# reTerm-HW-M-IOLINK-SUPPLY.net
KiCad netlist of a schematic drawn in Altium Designer
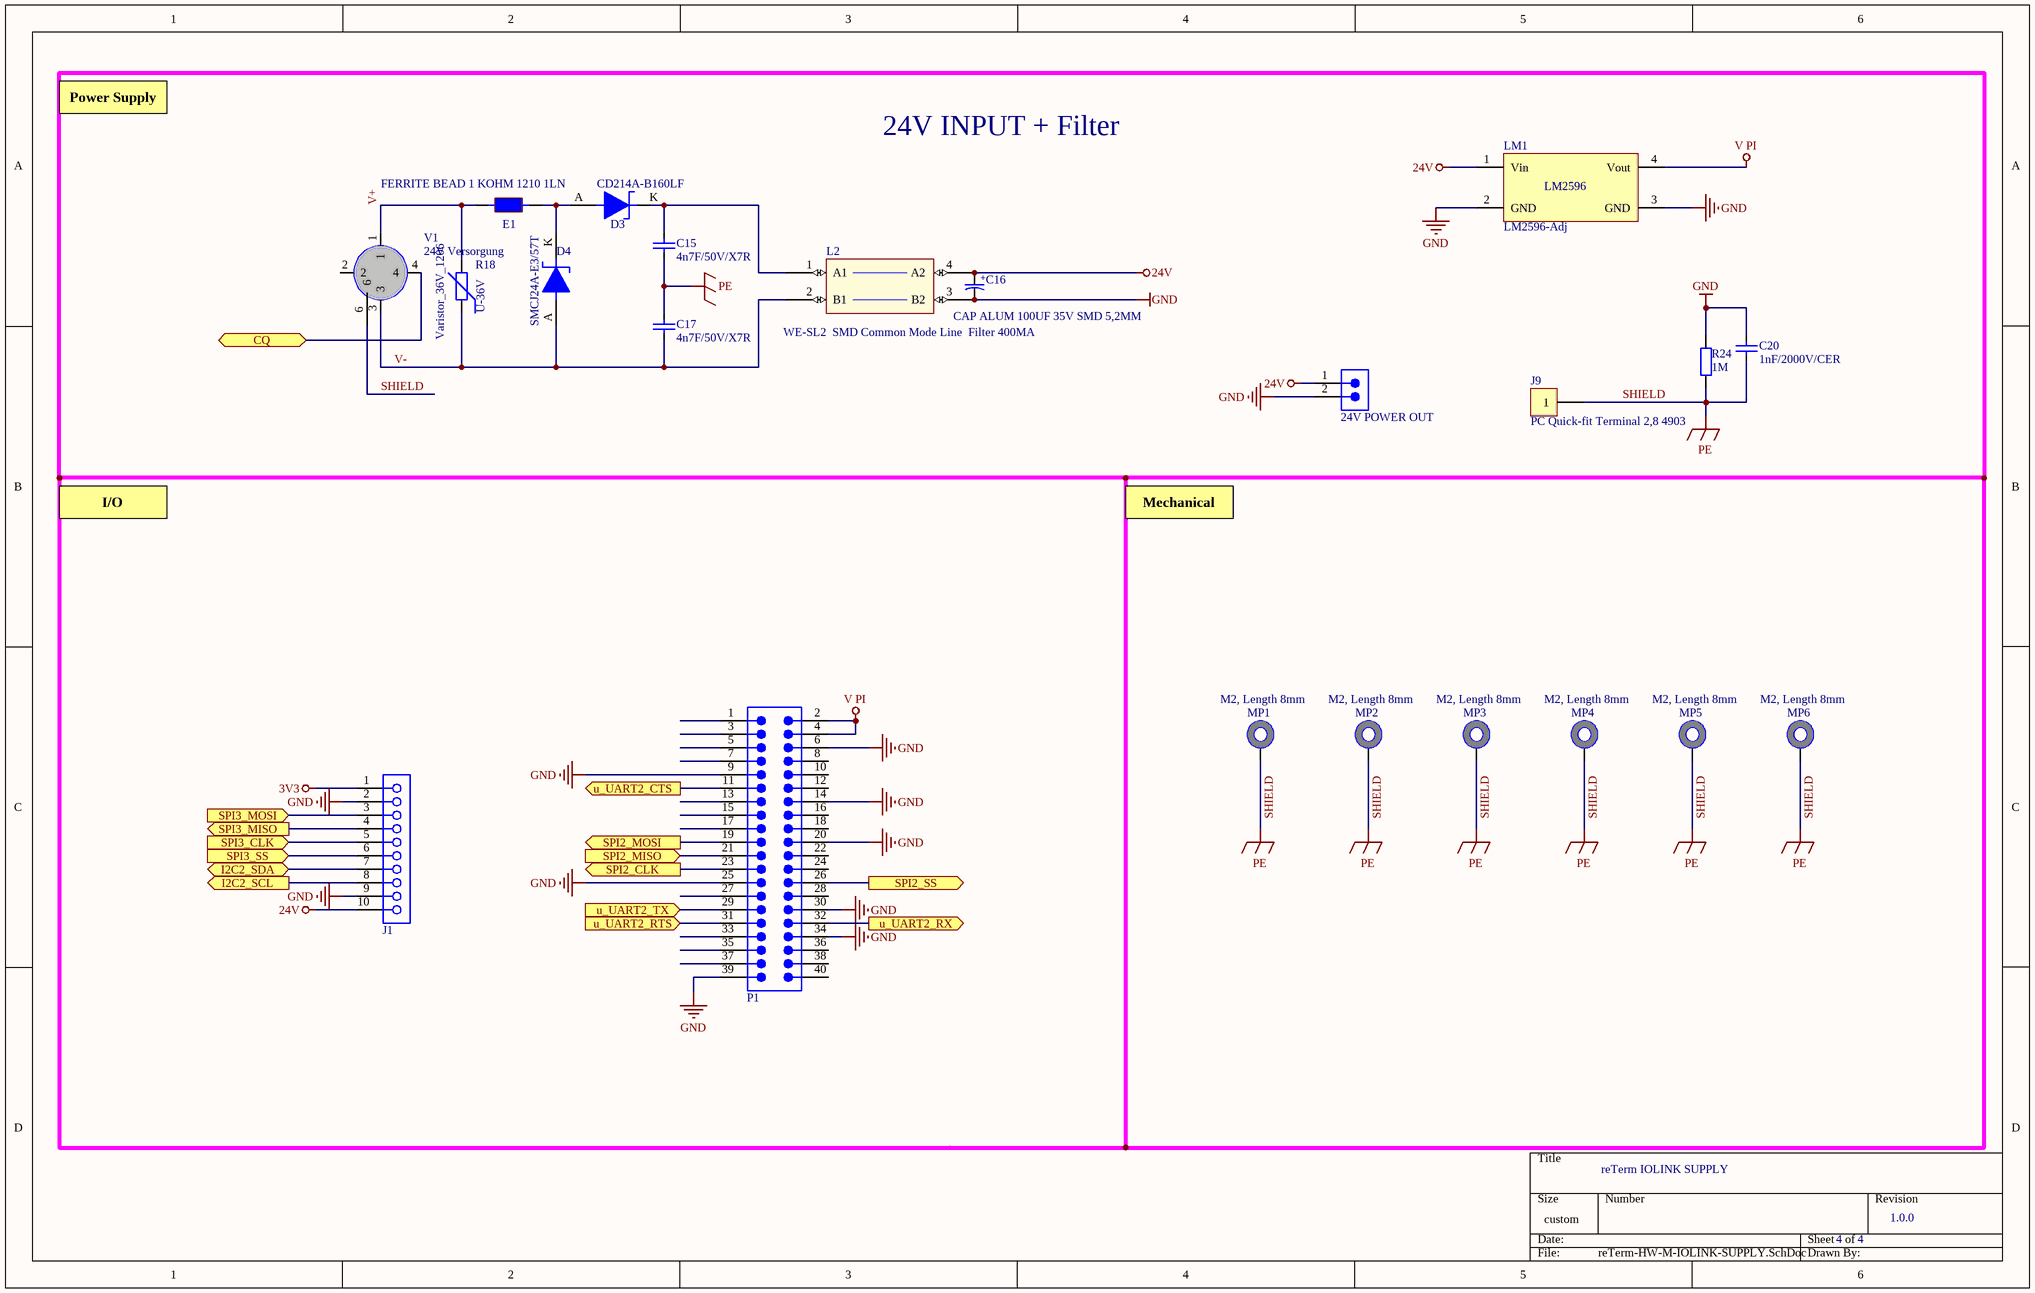
[diagram p0: reTerm-HW-M-IOLINK-SUPPLY.SchDoc]

(export (version "E")
  (design (tool "Eeschema 10.0.6"))
  (components
    (comp (ref "24V POWER OUT")
      (value "691322310002")
      (footprint "WR Terminal, 3.81mm, 2p")
      (description "WR-TBL Series 322 Horizontal PCB Header, THT, pitch 3.81mm, 2p")
      (fields (field (name "MANUFACTURER") "Wurth Elektronik"))
      (libsource (lib "HE_Lib") (part "WR Terminal, 3.81mm, 2p"))
    )
    (comp (ref "C15")
      (value "4n7F/50V/X7R")
      (footprint "C0603")
      (description "4n7F/50V/X7R 0603")
      (libsource (lib "HE_Lib") (part "CAP_4n7F_50V_X7R"))
    )
    (comp (ref "C16")
      (value "CAP ALUM 100UF 35V SMD 5,2MM")
      (footprint "SMD_ELKO_CASE_D8")
      (description "CAP ALUM 100UF 20% 35V SMD 5,2MM")
      (libsource (lib "HE_Lib") (part "CAP ALUM 100UF 20% 35V SMD 5,2MM"))
    )
    (comp (ref "C17")
      (value "4n7F/50V/X7R")
      (footprint "C0603")
      (description "4n7F/50V/X7R 0603")
      (libsource (lib "HE_Lib") (part "CAP_4n7F_50V_X7R"))
    )
    (comp (ref "C20")
      (value "1nF/2000V/CER")
      (footprint "C1206")
      (description "1nF/2000V/CER 1206")
      (libsource (lib "HE_Lib") (part "CAP_1nF_2000V_CER_1"))
    )
    (comp (ref "D3")
      (value "CD214A-B160LF")
      (footprint "DO-214AC")
      (description "DIODE SCHOTTKY 60V 1A SMA")
      (libsource (lib "HE_Lib") (part "CD214A-B160LF"))
    )
    (comp (ref "D4")
      (value "SMCJ24A-E3/57T")
      (footprint "DO-214AB")
      (description "TVS DIODE 24VWM 38.9VC SMC")
      (libsource (lib "HE_Lib") (part "SMCJ24A-E3/57T"))
    )
    (comp (ref "E1")
      (value "FERRITE BEAD 1 KOHM 1210 1LN")
      (footprint "L1210")
      (libsource (lib "HE_Lib") (part "FERRITE BEAD 1 KOHM 1210 1LN"))
    )
    (comp (ref "J1")
      (value "62001011821")
      (footprint "Header, 2.00 mm, THT, 10p")
      (description "WR-PHD Socket Header, THT, Vertical, pitch 2mm, 1 Row, 10P")
      (fields (field (name "MANUFACTURER") "Wurth Elektronik"))
      (libsource (lib "HE_Lib") (part "WR-PHD Header, THT, 2mm, 10P"))
    )
    (comp (ref "J9")
      (value "PC Quick-fit Terminal 2,8 4903")
      (footprint "PC-Quick-FIT-TERMINAL-4903")
      (description "PC Quick-Fit Terminal 2,8\r\nKeystone 4903")
      (libsource (lib "HE_Lib") (part "PC Quick-fit Terminal 2,8 4903"))
    )
    (comp (ref "L2")
      (value "WE-SL2  SMD Common Mode Line  Filter 400MA")
      (footprint "WE-SL2")
      (description "EMI Signal Line Filter WE-SL2 744229")
      (libsource (lib "HE_Lib") (part "WE-SL2 COMMON-CHOKE 400MA"))
    )
    (comp (ref "LM1")
      (value "LM2596-Adj")
      (footprint "lm2596")
      (description "Designed By @Alixahedi")
      (libsource (lib "HE_Lib") (part "LM2596-Adj"))
    )
    (comp (ref "MP1")
      (value "M2, Length 8mm")
      (footprint "9774080243")
      (description "WA-SMSI SMT Steel Spacer, M2 Thread Internal, Length 8mm")
      (fields (field (name "PARTNUMBER") "9774080243R") (field (name "PUBLISHER") "Wurth Elektronik"))
      (libsource (lib "WA-SMSI_M2 Thread Internal") (part "9774080243R"))
    )
    (comp (ref "MP2")
      (value "M2, Length 8mm")
      (footprint "9774080243")
      (description "WA-SMSI SMT Steel Spacer, M2 Thread Internal, Length 8mm")
      (fields (field (name "PARTNUMBER") "9774080243R") (field (name "PUBLISHER") "Wurth Elektronik"))
      (libsource (lib "WA-SMSI_M2 Thread Internal") (part "9774080243R"))
    )
    (comp (ref "MP3")
      (value "M2, Length 8mm")
      (footprint "9774080243")
      (description "WA-SMSI SMT Steel Spacer, M2 Thread Internal, Length 8mm")
      (fields (field (name "PARTNUMBER") "9774080243R") (field (name "PUBLISHER") "Wurth Elektronik"))
      (libsource (lib "WA-SMSI_M2 Thread Internal") (part "9774080243R"))
    )
    (comp (ref "MP4")
      (value "M2, Length 8mm")
      (footprint "9774080243")
      (description "WA-SMSI SMT Steel Spacer, M2 Thread Internal, Length 8mm")
      (fields (field (name "PARTNUMBER") "9774080243R") (field (name "PUBLISHER") "Wurth Elektronik"))
      (libsource (lib "WA-SMSI_M2 Thread Internal") (part "9774080243R"))
    )
    (comp (ref "MP5")
      (value "M2, Length 8mm")
      (footprint "9774080243")
      (description "WA-SMSI SMT Steel Spacer, M2 Thread Internal, Length 8mm")
      (fields (field (name "PARTNUMBER") "9774080243R") (field (name "PUBLISHER") "Wurth Elektronik"))
      (libsource (lib "WA-SMSI_M2 Thread Internal") (part "9774080243R"))
    )
    (comp (ref "MP6")
      (value "M2, Length 8mm")
      (footprint "9774080243")
      (description "WA-SMSI SMT Steel Spacer, M2 Thread Internal, Length 8mm")
      (fields (field (name "PARTNUMBER") "9774080243R") (field (name "PUBLISHER") "Wurth Elektronik"))
      (libsource (lib "WA-SMSI_M2 Thread Internal") (part "9774080243R"))
    )
    (comp (ref "P1")
      (value "61304021121")
      (footprint "WR-PHD Pin Header, THT, 2.54mm, 40P")
      (description "WR-PHD Pin Header, THT, Vertical, pitch 2.54mm, 2 Row, 40P")
      (fields (field (name "MANUFACTURER") "Wurth Elektronik"))
      (libsource (lib "HE_Lib") (part "WR-PHD Pin Header, 2.54mm, 40P"))
    )
    (comp (ref "R18")
      (value "Varistor_36V_1206")
      (footprint "V1206")
      (description "Varistor_36V_1206_82541300")
      (libsource (lib "HE_Lib") (part "Varistor_36V_1206"))
    )
    (comp (ref "R24")
      (value "1M")
      (footprint "R1206")
      (description "Resistor-1M")
      (libsource (lib "HE_Lib") (part "R1M"))
    )
    (comp (ref "V1")
      (value "24V Versorgung")
      (footprint "M12/4POL/A-COD/STECKER")
      (description "M12 Flanschdose 4-polig Serie 713/763")
      (libsource (lib "HE_Lib") (part "M12 Flanschdose 4 Serie 713/763"))
    )
  )
  (nets
    (net (code "1") (name "/CQ") (class "Default")
      (node (ref "V1") (pin "4") (pinfunction "4_4") (pintype "passive"))
    )
    (net (code "2") (name "/I2C2_SCL") (class "Default")
      (node (ref "J1") (pin "8") (pinfunction "8_8") (pintype "passive"))
    )
    (net (code "3") (name "/I2C2_SDA") (class "Default")
      (node (ref "J1") (pin "7") (pinfunction "7_7") (pintype "passive"))
    )
    (net (code "4") (name "/SPI2_CLK") (class "Default")
      (node (ref "P1") (pin "23") (pinfunction "23_23") (pintype "passive"))
    )
    (net (code "5") (name "/SPI2_MISO") (class "Default")
      (node (ref "P1") (pin "21") (pinfunction "21_21") (pintype "passive"))
    )
    (net (code "6") (name "/SPI2_MOSI") (class "Default")
      (node (ref "P1") (pin "19") (pinfunction "19_19") (pintype "passive"))
    )
    (net (code "7") (name "/SPI2_SS") (class "Default")
      (node (ref "P1") (pin "26") (pinfunction "26_26") (pintype "passive"))
    )
    (net (code "8") (name "/SPI3_CLK") (class "Default")
      (node (ref "J1") (pin "5") (pinfunction "5_5") (pintype "passive"))
    )
    (net (code "9") (name "/SPI3_MISO") (class "Default")
      (node (ref "J1") (pin "4") (pinfunction "4_4") (pintype "passive"))
    )
    (net (code "10") (name "/SPI3_MOSI") (class "Default")
      (node (ref "J1") (pin "3") (pinfunction "3_3") (pintype "passive"))
    )
    (net (code "11") (name "/SPI3_SS") (class "Default")
      (node (ref "J1") (pin "6") (pinfunction "6_6") (pintype "passive"))
    )
    (net (code "12") (name "/V+") (class "Default")
      (node (ref "E1") (pin "1") (pinfunction "1_1") (pintype "passive"))
      (node (ref "R18") (pin "2") (pinfunction "2_2") (pintype "passive"))
      (node (ref "V1") (pin "1") (pinfunction "1_1") (pintype "passive"))
    )
    (net (code "13") (name "/V-") (class "Default")
      (node (ref "C17") (pin "2") (pinfunction "2_2") (pintype "passive"))
      (node (ref "D4") (pin "A") (pinfunction "A_A") (pintype "passive"))
      (node (ref "L2") (pin "2") (pinfunction "B1_2") (pintype "bidirectional"))
      (node (ref "R18") (pin "1") (pinfunction "1_1") (pintype "passive"))
      (node (ref "V1") (pin "3") (pinfunction "3_3") (pintype "passive"))
    )
    (net (code "14") (name "/u_UART2_CTS") (class "Default")
      (node (ref "P1") (pin "11") (pinfunction "11_11") (pintype "passive"))
    )
    (net (code "15") (name "/u_UART2_RTS") (class "Default")
      (node (ref "P1") (pin "31") (pinfunction "31_31") (pintype "passive"))
    )
    (net (code "16") (name "/u_UART2_RX") (class "Default")
      (node (ref "P1") (pin "32") (pinfunction "32_32") (pintype "passive"))
    )
    (net (code "17") (name "/u_UART2_TX") (class "Default")
      (node (ref "P1") (pin "29") (pinfunction "29_29") (pintype "passive"))
    )
    (net (code "18") (name "3V3") (class "Default")
      (node (ref "J1") (pin "1") (pinfunction "1_1") (pintype "passive"))
    )
    (net (code "19") (name "24V") (class "Default")
      (node (ref "24V POWER OUT") (pin "1") (pinfunction "1_1") (pintype "passive"))
      (node (ref "C16") (pin "1") (pinfunction "1_1") (pintype "passive"))
      (node (ref "J1") (pin "10") (pinfunction "10_10") (pintype "passive"))
      (node (ref "L2") (pin "4") (pinfunction "A2_4") (pintype "bidirectional"))
      (node (ref "LM1") (pin "1") (pinfunction "Vin_1") (pintype "passive"))
    )
    (net (code "20") (name "GND") (class "Default")
      (node (ref "24V POWER OUT") (pin "2") (pinfunction "2_2") (pintype "passive"))
      (node (ref "C16") (pin "2") (pinfunction "2_2") (pintype "passive"))
      (node (ref "C20") (pin "2") (pinfunction "2_2") (pintype "passive"))
      (node (ref "J1") (pin "2") (pinfunction "2_2") (pintype "passive"))
      (node (ref "J1") (pin "9") (pinfunction "9_9") (pintype "passive"))
      (node (ref "L2") (pin "3") (pinfunction "B2_3") (pintype "bidirectional"))
      (node (ref "LM1") (pin "2") (pinfunction "GND_2") (pintype "passive"))
      (node (ref "LM1") (pin "3") (pinfunction "GND_3") (pintype "passive"))
      (node (ref "P1") (pin "14") (pinfunction "14_14") (pintype "passive"))
      (node (ref "P1") (pin "20") (pinfunction "20_20") (pintype "passive"))
      (node (ref "P1") (pin "25") (pinfunction "25_25") (pintype "passive"))
      (node (ref "P1") (pin "30") (pinfunction "30_30") (pintype "passive"))
      (node (ref "P1") (pin "34") (pinfunction "34_34") (pintype "passive"))
      (node (ref "P1") (pin "39") (pinfunction "39_39") (pintype "passive"))
      (node (ref "P1") (pin "6") (pinfunction "6_6") (pintype "passive"))
      (node (ref "P1") (pin "9") (pinfunction "9_9") (pintype "passive"))
      (node (ref "R24") (pin "2") (pinfunction "2_2") (pintype "passive"))
    )
    (net (code "21") (name "Net-(D3-PadA)") (class "Default")
      (node (ref "D3") (pin "A") (pinfunction "A_A") (pintype "passive"))
      (node (ref "D4") (pin "K") (pinfunction "K_K") (pintype "passive"))
      (node (ref "E1") (pin "2") (pinfunction "1_2") (pintype "passive"))
    )
    (net (code "22") (name "Net-(L2-A1)") (class "Default")
      (node (ref "C15") (pin "2") (pinfunction "2_2") (pintype "passive"))
      (node (ref "D3") (pin "K") (pinfunction "K_K") (pintype "passive"))
      (node (ref "L2") (pin "1") (pinfunction "A1_1") (pintype "bidirectional"))
    )
    (net (code "23") (name "PE") (class "Default")
      (node (ref "C15") (pin "1") (pinfunction "1_1") (pintype "passive"))
      (node (ref "C17") (pin "1") (pinfunction "1_1") (pintype "passive"))
      (node (ref "C20") (pin "1") (pinfunction "1_1") (pintype "passive"))
      (node (ref "J9") (pin "1") (pinfunction "1_1") (pintype "passive"))
      (node (ref "MP1") (pin "1") (pinfunction "1_1") (pintype "passive"))
      (node (ref "MP2") (pin "1") (pinfunction "1_1") (pintype "passive"))
      (node (ref "MP3") (pin "1") (pinfunction "1_1") (pintype "passive"))
      (node (ref "MP4") (pin "1") (pinfunction "1_1") (pintype "passive"))
      (node (ref "MP5") (pin "1") (pinfunction "1_1") (pintype "passive"))
      (node (ref "MP6") (pin "1") (pinfunction "1_1") (pintype "passive"))
      (node (ref "R24") (pin "1") (pinfunction "1_1") (pintype "passive"))
      (node (ref "V1") (pin "6") (pinfunction "6_6") (pintype "passive"))
    )
    (net (code "24") (name "V PI") (class "Default")
      (node (ref "LM1") (pin "4") (pinfunction "Vout_4") (pintype "passive"))
      (node (ref "P1") (pin "2") (pinfunction "2_2") (pintype "passive"))
      (node (ref "P1") (pin "4") (pinfunction "4_4") (pintype "passive"))
    )
    (net (code "25") (name "unconnected-(P1-Pad1)") (class "Default")
      (node (ref "P1") (pin "1") (pinfunction "1_1") (pintype "passive"))
    )
    (net (code "26") (name "unconnected-(P1-Pad3)") (class "Default")
      (node (ref "P1") (pin "3") (pinfunction "3_3") (pintype "passive"))
    )
    (net (code "27") (name "unconnected-(P1-Pad5)") (class "Default")
      (node (ref "P1") (pin "5") (pinfunction "5_5") (pintype "passive"))
    )
    (net (code "28") (name "unconnected-(P1-Pad7)") (class "Default")
      (node (ref "P1") (pin "7") (pinfunction "7_7") (pintype "passive"))
    )
    (net (code "29") (name "unconnected-(P1-Pad8)") (class "Default")
      (node (ref "P1") (pin "8") (pinfunction "8_8") (pintype "passive"))
    )
    (net (code "30") (name "unconnected-(P1-Pad10)") (class "Default")
      (node (ref "P1") (pin "10") (pinfunction "10_10") (pintype "passive"))
    )
    (net (code "31") (name "unconnected-(P1-Pad12)") (class "Default")
      (node (ref "P1") (pin "12") (pinfunction "12_12") (pintype "passive"))
    )
    (net (code "32") (name "unconnected-(P1-Pad13)") (class "Default")
      (node (ref "P1") (pin "13") (pinfunction "13_13") (pintype "passive"))
    )
    (net (code "33") (name "unconnected-(P1-Pad15)") (class "Default")
      (node (ref "P1") (pin "15") (pinfunction "15_15") (pintype "passive"))
    )
    (net (code "34") (name "unconnected-(P1-Pad16)") (class "Default")
      (node (ref "P1") (pin "16") (pinfunction "16_16") (pintype "passive"))
    )
    (net (code "35") (name "unconnected-(P1-Pad17)") (class "Default")
      (node (ref "P1") (pin "17") (pinfunction "17_17") (pintype "passive"))
    )
    (net (code "36") (name "unconnected-(P1-Pad18)") (class "Default")
      (node (ref "P1") (pin "18") (pinfunction "18_18") (pintype "passive"))
    )
    (net (code "37") (name "unconnected-(P1-Pad22)") (class "Default")
      (node (ref "P1") (pin "22") (pinfunction "22_22") (pintype "passive"))
    )
    (net (code "38") (name "unconnected-(P1-Pad24)") (class "Default")
      (node (ref "P1") (pin "24") (pinfunction "24_24") (pintype "passive"))
    )
    (net (code "39") (name "unconnected-(P1-Pad27)") (class "Default")
      (node (ref "P1") (pin "27") (pinfunction "27_27") (pintype "passive"))
    )
    (net (code "40") (name "unconnected-(P1-Pad28)") (class "Default")
      (node (ref "P1") (pin "28") (pinfunction "28_28") (pintype "passive"))
    )
    (net (code "41") (name "unconnected-(P1-Pad33)") (class "Default")
      (node (ref "P1") (pin "33") (pinfunction "33_33") (pintype "passive"))
    )
    (net (code "42") (name "unconnected-(P1-Pad35)") (class "Default")
      (node (ref "P1") (pin "35") (pinfunction "35_35") (pintype "passive"))
    )
    (net (code "43") (name "unconnected-(P1-Pad36)") (class "Default")
      (node (ref "P1") (pin "36") (pinfunction "36_36") (pintype "passive"))
    )
    (net (code "44") (name "unconnected-(P1-Pad37)") (class "Default")
      (node (ref "P1") (pin "37") (pinfunction "37_37") (pintype "passive"))
    )
    (net (code "45") (name "unconnected-(P1-Pad38)") (class "Default")
      (node (ref "P1") (pin "38") (pinfunction "38_38") (pintype "passive"))
    )
    (net (code "46") (name "unconnected-(P1-Pad40)") (class "Default")
      (node (ref "P1") (pin "40") (pinfunction "40_40") (pintype "passive"))
    )
    (net (code "47") (name "unconnected-(V1-Pad2)") (class "Default")
      (node (ref "V1") (pin "2") (pinfunction "2_2") (pintype "passive"))
    )
  )
)
